# Puzzle_-_Infrared_Emitter_v0_9b.net
KiCad netlist of a schematic drawn in EAGLE
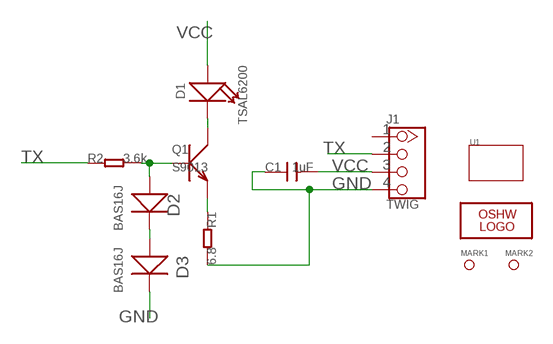
[diagram p0: schematic, sheet 1]

(export (version "E")
  (design (tool "Eeschema 10.0.6"))
  (components
    (comp (ref "C1")
      (value "1uF")
      (footprint "eagle-import:0603")
      (libsource (lib "eagle-import") (part "C-0603"))
    )
    (comp (ref "D1")
      (value "TSAL6200")
      (footprint "eagle-import:2P-LEADED-ROUND-2.54-R3.0")
      (libsource (lib "eagle-import") (part "LED-2.54"))
    )
    (comp (ref "D2")
      (value "BAS16J")
      (footprint "eagle-import:D0805")
      (libsource (lib "eagle-import") (part "D-0805"))
    )
    (comp (ref "D3")
      (value "BAS16J")
      (footprint "eagle-import:D0805")
      (libsource (lib "eagle-import") (part "D-0805"))
    )
    (comp (ref "J1")
      (value "TWIG")
      (footprint "eagle-import:4P-LEADED-2.0")
      (libsource (lib "eagle-import") (part "TWIG-2.0-LEADED-2.0"))
    )
    (comp (ref "LOGO1")
      (value "LOGO-OSHW-FILLX0150-NT")
      (footprint "eagle-import:OSHW_FILLX150_NOTEXT")
      (libsource (lib "eagle-import") (part "LOGO-OSHW-FILLX0150-NT"))
    )
    (comp (ref "MARK1")
      (value "PAD-MARK")
      (footprint "eagle-import:ROUND-MARK-0.635")
      (libsource (lib "eagle-import") (part "PAD-MARK"))
    )
    (comp (ref "MARK2")
      (value "PAD-MARK")
      (footprint "eagle-import:ROUND-MARK-0.635")
      (libsource (lib "eagle-import") (part "PAD-MARK"))
    )
    (comp (ref "Q1")
      (value "S9013")
      (footprint "eagle-import:SOT23")
      (libsource (lib "eagle-import") (part "TRANSISTOR-NPN-SOT23''"))
    )
    (comp (ref "R1")
      (value "6.8")
      (footprint "eagle-import:0805")
      (libsource (lib "eagle-import") (part "R-0805"))
    )
    (comp (ref "R2")
      (value "3.6k")
      (footprint "eagle-import:0603")
      (libsource (lib "eagle-import") (part "R-0603"))
    )
    (comp (ref "U1")
      (value "TWIG-1U")
      (footprint "eagle-import:1U-DIM-W_-DRILL")
      (libsource (lib "eagle-import") (part "TWIG-1U"))
    )
  )
  (nets
    (net (code "1") (name "/GND") (class "Default")
      (node (ref "C1") (pin "1") (pinfunction "1_1") (pintype "passive"))
      (node (ref "D3") (pin "-") (pinfunction "-_-") (pintype "passive"))
      (node (ref "J1") (pin "4") (pinfunction "4_4") (pintype "bidirectional"))
      (node (ref "R1") (pin "2") (pinfunction "2_2") (pintype "passive"))
    )
    (net (code "2") (name "/TX") (class "Default")
      (node (ref "J1") (pin "2") (pinfunction "2_2") (pintype "bidirectional"))
      (node (ref "R2") (pin "1") (pinfunction "1_1") (pintype "passive"))
    )
    (net (code "3") (name "/VCC") (class "Default")
      (node (ref "C1") (pin "2") (pinfunction "2_2") (pintype "passive"))
      (node (ref "D1") (pin "+") (pinfunction "+_+") (pintype "passive"))
      (node (ref "J1") (pin "3") (pinfunction "3_3") (pintype "bidirectional"))
    )
    (net (code "4") (name "Net-(D2-Pad-)") (class "Default")
      (node (ref "D2") (pin "-") (pinfunction "-_-") (pintype "passive"))
      (node (ref "D3") (pin "+") (pinfunction "+_+") (pintype "passive"))
    )
    (net (code "5") (name "Net-(Q1-B)") (class "Default")
      (node (ref "D2") (pin "+") (pinfunction "+_+") (pintype "passive"))
      (node (ref "Q1") (pin "1") (pinfunction "B_1") (pintype "passive"))
      (node (ref "R2") (pin "2") (pinfunction "2_2") (pintype "passive"))
    )
    (net (code "6") (name "Net-(Q1-C)") (class "Default")
      (node (ref "D1") (pin "-") (pinfunction "-_-") (pintype "passive"))
      (node (ref "Q1") (pin "3") (pinfunction "C_3") (pintype "passive"))
    )
    (net (code "7") (name "Net-(Q1-E)") (class "Default")
      (node (ref "Q1") (pin "2") (pinfunction "E_2") (pintype "passive"))
      (node (ref "R1") (pin "1") (pinfunction "1_1") (pintype "passive"))
    )
    (net (code "8") (name "unconnected-(J1-Pad1)") (class "Default")
      (node (ref "J1") (pin "1") (pinfunction "1_1") (pintype "bidirectional"))
    )
  )
)
